# OwlOrbOfProtection.net
KiCad netlist of a schematic drawn in EAGLE
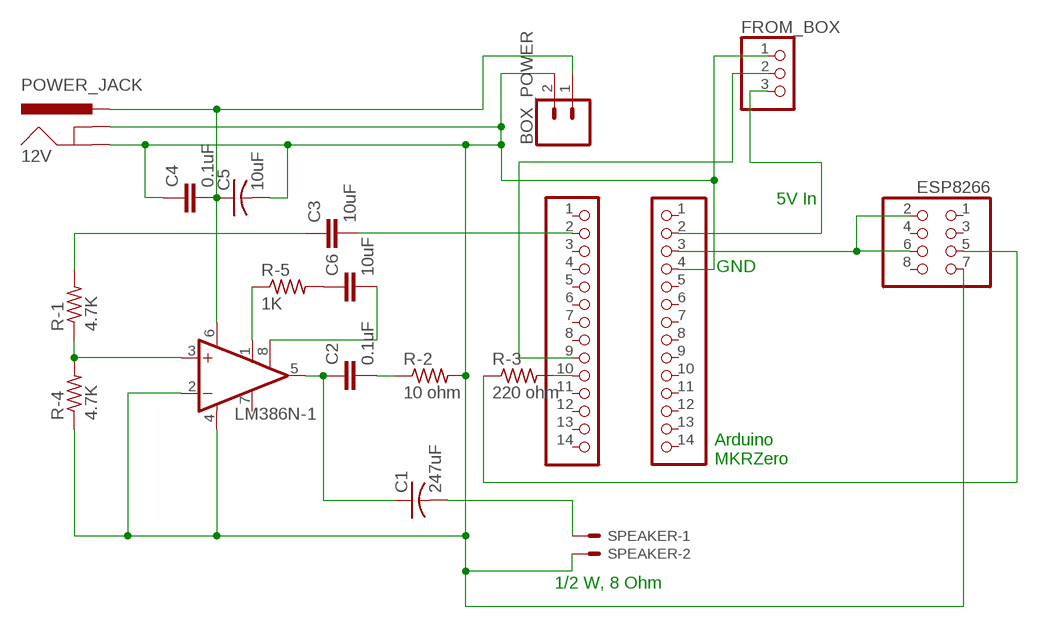
[diagram p0: schematic, sheet 1]

(export (version "E")
  (design (tool "Eeschema 10.0.6"))
  (components
    (comp (ref "12V")
      (value "POWER_JACK")
      (footprint "eagle-import:POWER_JACK_PTH")
      (libsource (lib "eagle-import") (part "POWER_JACK"))
    )
    (comp (ref "BOX_POWER")
      (value "CONN_023.5MM")
      (footprint "eagle-import:SCREWTERMINAL-3.5MM-2")
      (libsource (lib "eagle-import") (part "CONN_023.5MM"))
    )
    (comp (ref "C1")
      (value "247uF")
      (footprint "eagle-import:C025-024X044")
      (libsource (lib "eagle-import") (part "C-US025-024X044"))
    )
    (comp (ref "C2")
      (value "0.1uF")
      (footprint "eagle-import:C2.5-3")
      (libsource (lib "eagle-import") (part "C2,5-3"))
    )
    (comp (ref "C3")
      (value "10uF")
      (footprint "eagle-import:C2.5-3")
      (libsource (lib "eagle-import") (part "C2,5-3"))
    )
    (comp (ref "C4")
      (value "0.1uF")
      (footprint "eagle-import:C2.5-3")
      (libsource (lib "eagle-import") (part "C2,5-3"))
    )
    (comp (ref "C5")
      (value "10uF")
      (footprint "eagle-import:C025-024X044")
      (libsource (lib "eagle-import") (part "C-US025-024X044"))
    )
    (comp (ref "C6")
      (value "10uF")
      (footprint "eagle-import:C2.5-3")
      (libsource (lib "eagle-import") (part "C2,5-3"))
    )
    (comp (ref "ESP8266")
      (value "PINHD-2X4")
      (footprint "eagle-import:2X04")
      (libsource (lib "eagle-import") (part "PINHD-2X4"))
    )
    (comp (ref "FROM_BOX")
      (value "PINHD-1X3")
      (footprint "eagle-import:1X03")
      (libsource (lib "eagle-import") (part "PINHD-1X3"))
    )
    (comp (ref "IC2")
      (value "LM386N-1")
      (footprint "eagle-import:DIL08")
      (libsource (lib "eagle-import") (part "LM386?-N1"))
    )
    (comp (ref "JP1")
      (value "PINHD-1X14")
      (footprint "eagle-import:1X14")
      (libsource (lib "eagle-import") (part "PINHD-1X14"))
    )
    (comp (ref "JP2")
      (value "PINHD-1X14")
      (footprint "eagle-import:1X14")
      (libsource (lib "eagle-import") (part "PINHD-1X14"))
    )
    (comp (ref "R-1")
      (value "4.7K")
      (footprint "eagle-import:0207_10")
      (libsource (lib "eagle-import") (part "R-US_0207/10"))
    )
    (comp (ref "R-2")
      (value "10 ohm")
      (footprint "eagle-import:0207_10")
      (libsource (lib "eagle-import") (part "R-US_0207/10"))
    )
    (comp (ref "R-3")
      (value "220 ohm")
      (footprint "eagle-import:0207_10")
      (libsource (lib "eagle-import") (part "R-US_0207/10"))
    )
    (comp (ref "R-4")
      (value "4.7K")
      (footprint "eagle-import:0207_10")
      (libsource (lib "eagle-import") (part "R-US_0207/10"))
    )
    (comp (ref "R-5")
      (value "1K")
      (footprint "eagle-import:0207_10")
      (libsource (lib "eagle-import") (part "R-US_0207/10"))
    )
    (comp (ref "SPEAKER")
      (value "22-23-2021")
      (footprint "eagle-import:22-23-2021")
      (fields (field (name "MF") "MOLEX"))
      (libsource (lib "eagle-import") (part "22-23-2021"))
    )
  )
  (nets
    (net (code "1") (name "Net-(C2-Pad2)") (class "Default")
      (node (ref "C2") (pin "2") (pinfunction "2_2") (pintype "passive"))
      (node (ref "R-2") (pin "1") (pinfunction "1_1") (pintype "passive"))
    )
    (net (code "2") (name "Net-(C3-Pad1)") (class "Default")
      (node (ref "C3") (pin "1") (pinfunction "1_1") (pintype "passive"))
      (node (ref "R-1") (pin "2") (pinfunction "2_2") (pintype "passive"))
    )
    (net (code "3") (name "Net-(C3-Pad2)") (class "Default")
      (node (ref "C3") (pin "2") (pinfunction "2_2") (pintype "passive"))
      (node (ref "JP1") (pin "2") (pinfunction "2_2") (pintype "passive"))
    )
    (net (code "4") (name "Net-(C6-Pad1)") (class "Default")
      (node (ref "C6") (pin "1") (pinfunction "1_1") (pintype "passive"))
      (node (ref "R-5") (pin "2") (pinfunction "2_2") (pintype "passive"))
    )
    (net (code "5") (name "Net-(C6-Pad2)") (class "Default")
      (node (ref "C6") (pin "2") (pinfunction "2_2") (pintype "passive"))
      (node (ref "IC2") (pin "8") (pinfunction "GAIN_8") (pintype "passive"))
    )
    (net (code "6") (name "Net-(ESP8266-Pad2)") (class "Default")
      (node (ref "ESP8266") (pin "2") (pinfunction "2_2") (pintype "passive"))
      (node (ref "ESP8266") (pin "6") (pinfunction "6_6") (pintype "passive"))
      (node (ref "JP2") (pin "3") (pinfunction "3_3") (pintype "passive"))
    )
    (net (code "7") (name "Net-(ESP8266-Pad5)") (class "Default")
      (node (ref "ESP8266") (pin "5") (pinfunction "5_5") (pintype "passive"))
      (node (ref "R-3") (pin "1") (pinfunction "1_1") (pintype "passive"))
    )
    (net (code "8") (name "Net-(FROM_BOX-Pad2)") (class "Default")
      (node (ref "FROM_BOX") (pin "2") (pinfunction "2_2") (pintype "passive"))
      (node (ref "JP1") (pin "9") (pinfunction "9_9") (pintype "passive"))
    )
    (net (code "9") (name "Net-(FROM_BOX-Pad3)") (class "Default")
      (node (ref "FROM_BOX") (pin "3") (pinfunction "3_3") (pintype "passive"))
      (node (ref "JP2") (pin "2") (pinfunction "2_2") (pintype "passive"))
    )
    (net (code "10") (name "Net-(IC2-+IN)") (class "Default")
      (node (ref "IC2") (pin "3") (pinfunction "+IN_3") (pintype "input"))
      (node (ref "R-1") (pin "1") (pinfunction "1_1") (pintype "passive"))
      (node (ref "R-4") (pin "2") (pinfunction "2_2") (pintype "passive"))
    )
    (net (code "11") (name "Net-(IC2--IN)") (class "Default")
      (node (ref "12V") (pin "GND") (pinfunction "GND_GND") (pintype "bidirectional"))
      (node (ref "12V") (pin "GNDBREAK") (pinfunction "GNDBREAK_GNDBREAK") (pintype "bidirectional"))
      (node (ref "BOX_POWER") (pin "2") (pinfunction "2_2") (pintype "passive"))
      (node (ref "C4") (pin "1") (pinfunction "1_1") (pintype "passive"))
      (node (ref "C5") (pin "2") (pinfunction "2_2") (pintype "passive"))
      (node (ref "ESP8266") (pin "7") (pinfunction "7_7") (pintype "passive"))
      (node (ref "FROM_BOX") (pin "1") (pinfunction "1_1") (pintype "passive"))
      (node (ref "IC2") (pin "2") (pinfunction "-IN_2") (pintype "input"))
      (node (ref "IC2") (pin "4") (pinfunction "GND_4") (pintype "power_in"))
      (node (ref "JP2") (pin "4") (pinfunction "4_4") (pintype "passive"))
      (node (ref "R-2") (pin "2") (pinfunction "2_2") (pintype "passive"))
      (node (ref "R-4") (pin "1") (pinfunction "1_1") (pintype "passive"))
      (node (ref "SPEAKER") (pin "2") (pinfunction "S_2") (pintype "passive"))
    )
    (net (code "12") (name "Net-(IC2-GAIN-Pad1)") (class "Default")
      (node (ref "IC2") (pin "1") (pinfunction "GAIN_1") (pintype "passive"))
      (node (ref "R-5") (pin "1") (pinfunction "1_1") (pintype "passive"))
    )
    (net (code "13") (name "Net-(IC2-OUT)") (class "Default")
      (node (ref "C1") (pin "1") (pinfunction "1_1") (pintype "passive"))
      (node (ref "C2") (pin "1") (pinfunction "1_1") (pintype "passive"))
      (node (ref "IC2") (pin "5") (pinfunction "OUT_5") (pintype "output"))
    )
    (net (code "14") (name "Net-(IC2-VS)") (class "Default")
      (node (ref "12V") (pin "PWR") (pinfunction "PWR_PWR") (pintype "bidirectional"))
      (node (ref "BOX_POWER") (pin "1") (pinfunction "1_1") (pintype "passive"))
      (node (ref "C4") (pin "2") (pinfunction "2_2") (pintype "passive"))
      (node (ref "C5") (pin "1") (pinfunction "1_1") (pintype "passive"))
      (node (ref "IC2") (pin "6") (pinfunction "VS_6") (pintype "power_in"))
    )
    (net (code "15") (name "Net-(JP1-Pad10)") (class "Default")
      (node (ref "JP1") (pin "10") (pinfunction "10_10") (pintype "passive"))
      (node (ref "R-3") (pin "2") (pinfunction "2_2") (pintype "passive"))
    )
    (net (code "16") (name "Net-(SPEAKERA-S)") (class "Default")
      (node (ref "C1") (pin "2") (pinfunction "2_2") (pintype "passive"))
      (node (ref "SPEAKER") (pin "1") (pinfunction "S_1") (pintype "passive"))
    )
    (net (code "17") (name "unconnected-(ESP8266-Pad1)") (class "Default")
      (node (ref "ESP8266") (pin "1") (pinfunction "1_1") (pintype "passive"))
    )
    (net (code "18") (name "unconnected-(ESP8266-Pad3)") (class "Default")
      (node (ref "ESP8266") (pin "3") (pinfunction "3_3") (pintype "passive"))
    )
    (net (code "19") (name "unconnected-(ESP8266-Pad4)") (class "Default")
      (node (ref "ESP8266") (pin "4") (pinfunction "4_4") (pintype "passive"))
    )
    (net (code "20") (name "unconnected-(ESP8266-Pad8)") (class "Default")
      (node (ref "ESP8266") (pin "8") (pinfunction "8_8") (pintype "passive"))
    )
    (net (code "21") (name "unconnected-(IC2-BYPASS-Pad7)") (class "Default")
      (node (ref "IC2") (pin "7") (pinfunction "BYPASS_7") (pintype "passive"))
    )
    (net (code "22") (name "unconnected-(JP1-Pad1)") (class "Default")
      (node (ref "JP1") (pin "1") (pinfunction "1_1") (pintype "passive"))
    )
    (net (code "23") (name "unconnected-(JP1-Pad3)") (class "Default")
      (node (ref "JP1") (pin "3") (pinfunction "3_3") (pintype "passive"))
    )
    (net (code "24") (name "unconnected-(JP1-Pad4)") (class "Default")
      (node (ref "JP1") (pin "4") (pinfunction "4_4") (pintype "passive"))
    )
    (net (code "25") (name "unconnected-(JP1-Pad5)") (class "Default")
      (node (ref "JP1") (pin "5") (pinfunction "5_5") (pintype "passive"))
    )
    (net (code "26") (name "unconnected-(JP1-Pad6)") (class "Default")
      (node (ref "JP1") (pin "6") (pinfunction "6_6") (pintype "passive"))
    )
    (net (code "27") (name "unconnected-(JP1-Pad7)") (class "Default")
      (node (ref "JP1") (pin "7") (pinfunction "7_7") (pintype "passive"))
    )
    (net (code "28") (name "unconnected-(JP1-Pad8)") (class "Default")
      (node (ref "JP1") (pin "8") (pinfunction "8_8") (pintype "passive"))
    )
    (net (code "29") (name "unconnected-(JP1-Pad11)") (class "Default")
      (node (ref "JP1") (pin "11") (pinfunction "11_11") (pintype "passive"))
    )
    (net (code "30") (name "unconnected-(JP1-Pad12)") (class "Default")
      (node (ref "JP1") (pin "12") (pinfunction "12_12") (pintype "passive"))
    )
    (net (code "31") (name "unconnected-(JP1-Pad13)") (class "Default")
      (node (ref "JP1") (pin "13") (pinfunction "13_13") (pintype "passive"))
    )
    (net (code "32") (name "unconnected-(JP1-Pad14)") (class "Default")
      (node (ref "JP1") (pin "14") (pinfunction "14_14") (pintype "passive"))
    )
    (net (code "33") (name "unconnected-(JP2-Pad1)") (class "Default")
      (node (ref "JP2") (pin "1") (pinfunction "1_1") (pintype "passive"))
    )
    (net (code "34") (name "unconnected-(JP2-Pad5)") (class "Default")
      (node (ref "JP2") (pin "5") (pinfunction "5_5") (pintype "passive"))
    )
    (net (code "35") (name "unconnected-(JP2-Pad6)") (class "Default")
      (node (ref "JP2") (pin "6") (pinfunction "6_6") (pintype "passive"))
    )
    (net (code "36") (name "unconnected-(JP2-Pad7)") (class "Default")
      (node (ref "JP2") (pin "7") (pinfunction "7_7") (pintype "passive"))
    )
    (net (code "37") (name "unconnected-(JP2-Pad8)") (class "Default")
      (node (ref "JP2") (pin "8") (pinfunction "8_8") (pintype "passive"))
    )
    (net (code "38") (name "unconnected-(JP2-Pad9)") (class "Default")
      (node (ref "JP2") (pin "9") (pinfunction "9_9") (pintype "passive"))
    )
    (net (code "39") (name "unconnected-(JP2-Pad10)") (class "Default")
      (node (ref "JP2") (pin "10") (pinfunction "10_10") (pintype "passive"))
    )
    (net (code "40") (name "unconnected-(JP2-Pad11)") (class "Default")
      (node (ref "JP2") (pin "11") (pinfunction "11_11") (pintype "passive"))
    )
    (net (code "41") (name "unconnected-(JP2-Pad12)") (class "Default")
      (node (ref "JP2") (pin "12") (pinfunction "12_12") (pintype "passive"))
    )
    (net (code "42") (name "unconnected-(JP2-Pad13)") (class "Default")
      (node (ref "JP2") (pin "13") (pinfunction "13_13") (pintype "passive"))
    )
    (net (code "43") (name "unconnected-(JP2-Pad14)") (class "Default")
      (node (ref "JP2") (pin "14") (pinfunction "14_14") (pintype "passive"))
    )
  )
)
